# Asfaloth_L2_AVI_ver0_0.net
KiCad netlist of a schematic drawn in Altium Designer
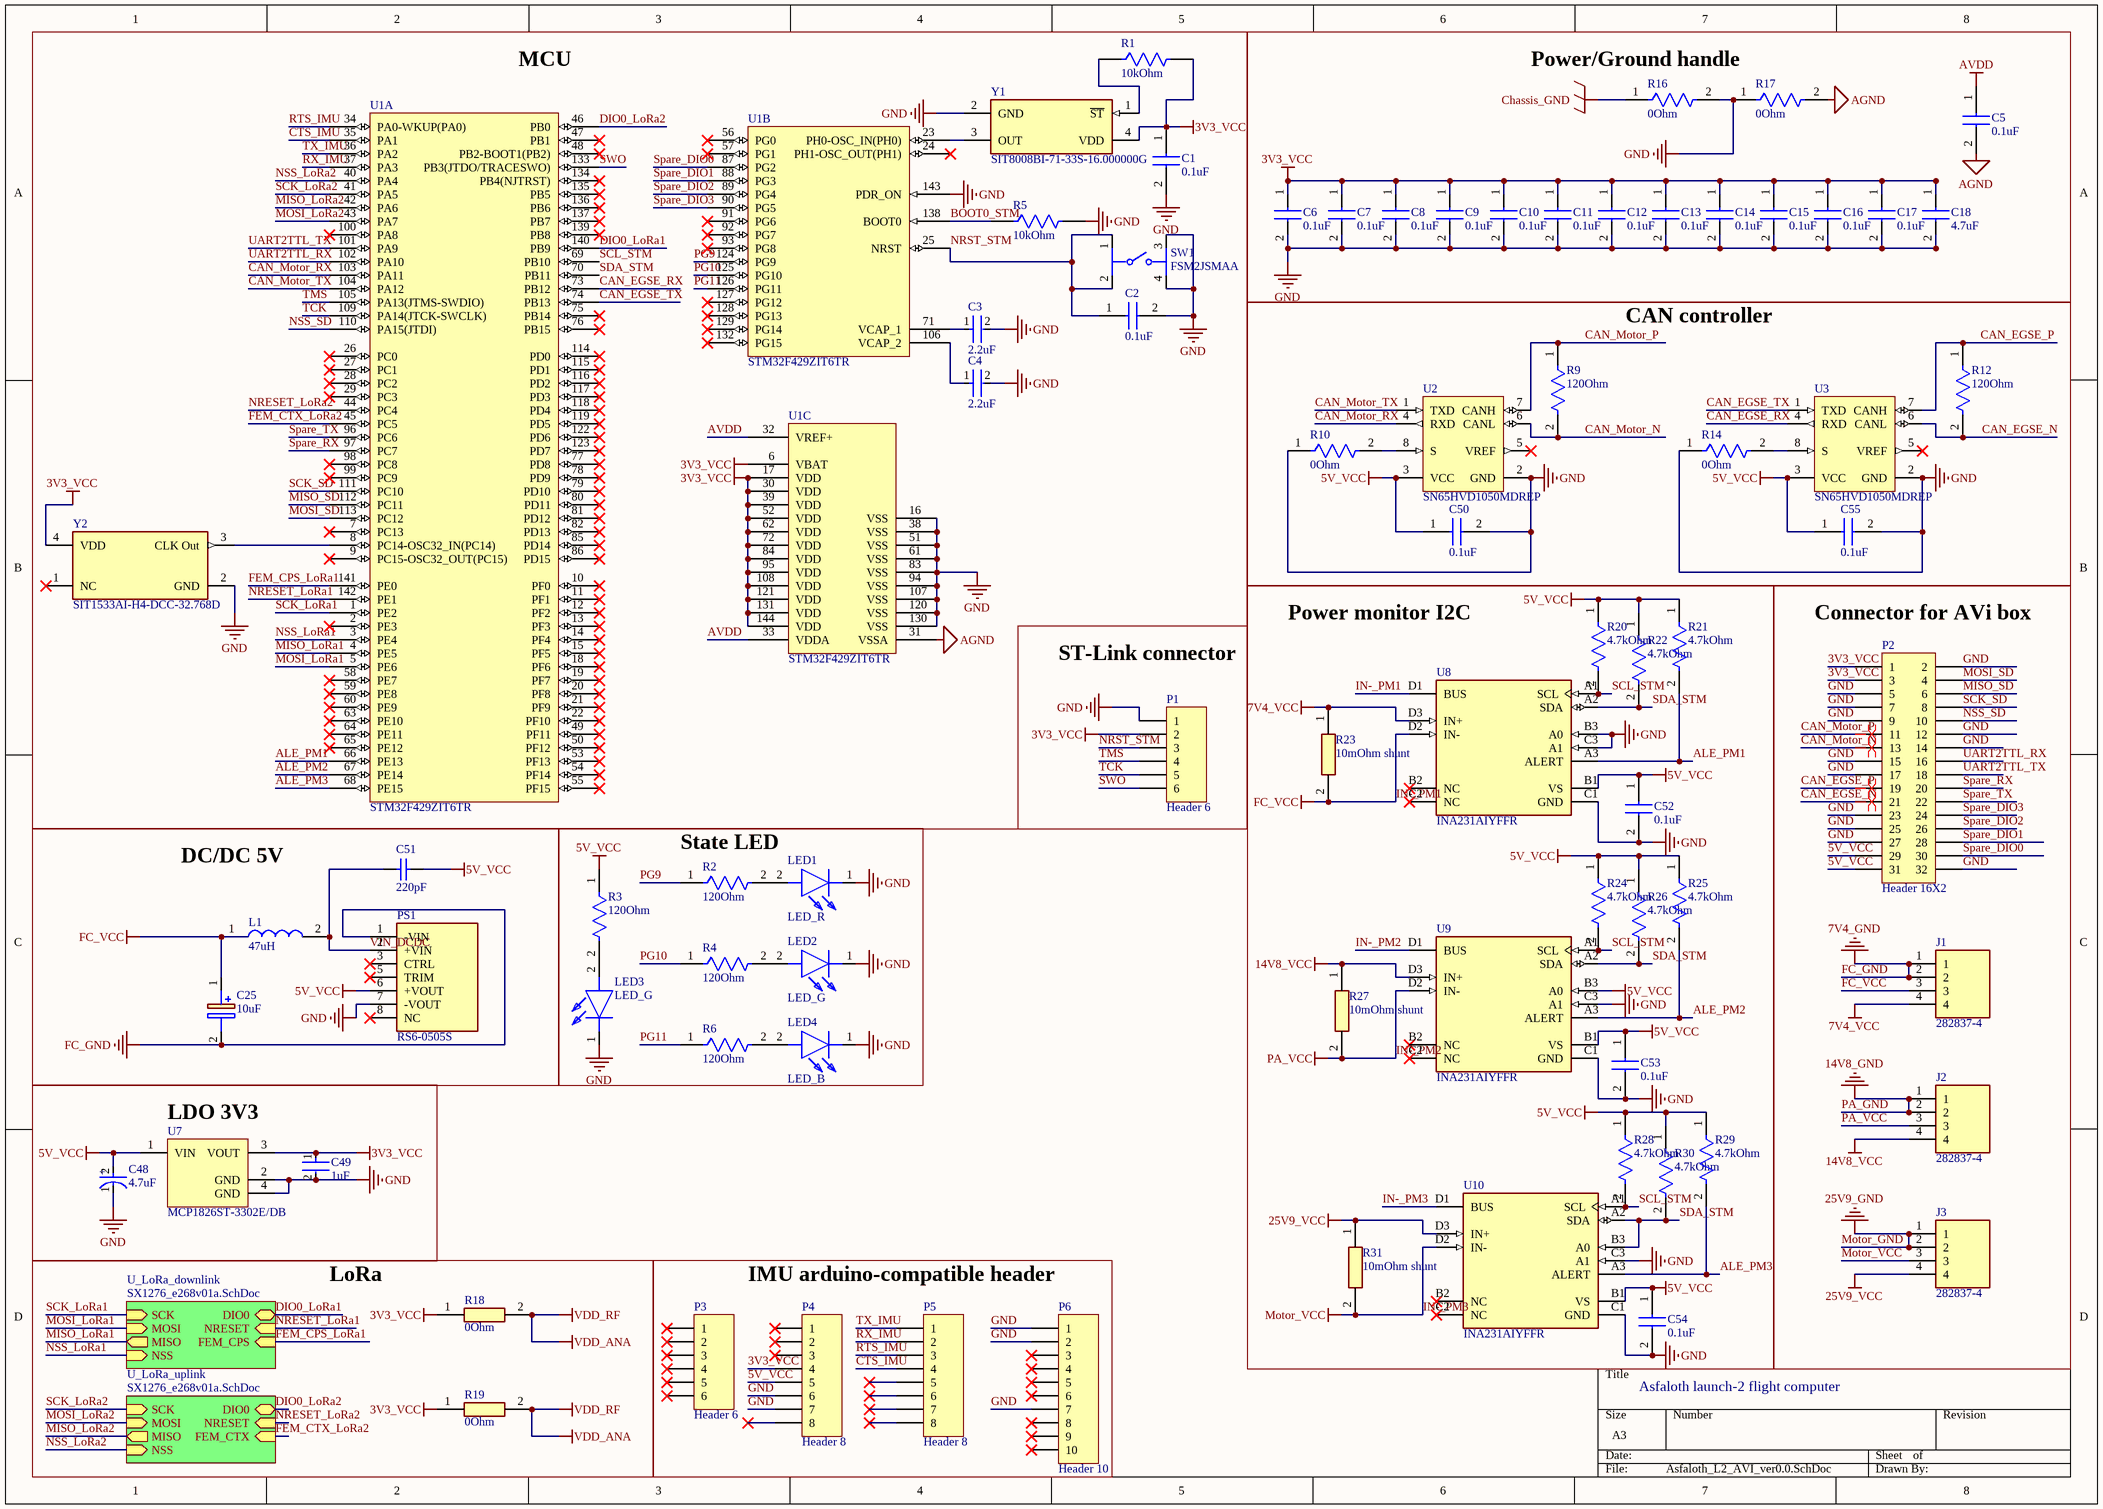
[diagram p0: Asfaloth_L2_AVI_ver0.0.SchDoc]

(export (version "E")
  (design (tool "Eeschema 10.0.6"))
  (components
    (comp (ref "C1")
      (value "0.1uF")
      (footprint "SamacSys:CAPC1608X87N")
      (description "Capacitor")
      (fields
        (field (name "MANUFACTURER_PART_NUMBER") "C0603C104J4RECAUTO")
        (field (name "MOUSER PART NUMBER") "80-C0603C104J4RECAUT")
      )
      (libsource (lib "*") (part "C0603C104J4RECAUTO"))
    )
    (comp (ref "C2")
      (value "0.1uF")
      (footprint "SamacSys:CAPC1608X87N")
      (description "Capacitor")
      (fields
        (field (name "MANUFACTURER_PART_NUMBER") "C0603C104J4RECAUTO")
        (field (name "MOUSER PART NUMBER") "80-C0603C104J4RECAUT")
      )
      (libsource (lib "*") (part "C0603C104J4RECAUTO"))
    )
    (comp (ref "C3")
      (value "2.2uF")
      (footprint "FP-GRT155-0_2-IPC_C")
      (description "Multi-Layer Ceramic Capacitor 2.2uF 10V X6S ±10% 0402 Paper T/R")
      (fields (field (name "TOLERANCE") "10%"))
      (libsource (lib "Altium Content Vault") (part "02cd4be3c70576c341d710602a673aa"))
    )
    (comp (ref "C4")
      (value "2.2uF")
      (footprint "FP-GRT155-0_2-IPC_C")
      (description "Multi-Layer Ceramic Capacitor 2.2uF 10V X6S ±10% 0402 Paper T/R")
      (fields (field (name "TOLERANCE") "10%"))
      (libsource (lib "Altium Content Vault") (part "02cd4be3c70576c341d710602a673aa"))
    )
    (comp (ref "C5")
      (value "0.1uF")
      (footprint "SamacSys:CAPC1608X87N")
      (description "Capacitor")
      (fields
        (field (name "MANUFACTURER_PART_NUMBER") "C0603C104J4RECAUTO")
        (field (name "MOUSER PART NUMBER") "80-C0603C104J4RECAUT")
      )
      (libsource (lib "*") (part "C0603C104J4RECAUTO"))
    )
    (comp (ref "C6")
      (value "0.1uF")
      (footprint "SamacSys:CAPC1608X87N")
      (description "Capacitor")
      (fields
        (field (name "MANUFACTURER_PART_NUMBER") "C0603C104J4RECAUTO")
        (field (name "MOUSER PART NUMBER") "80-C0603C104J4RECAUT")
      )
      (libsource (lib "*") (part "C0603C104J4RECAUTO"))
    )
    (comp (ref "C7")
      (value "0.1uF")
      (footprint "SamacSys:CAPC1608X87N")
      (description "Capacitor")
      (fields
        (field (name "MANUFACTURER_PART_NUMBER") "C0603C104J4RECAUTO")
        (field (name "MOUSER PART NUMBER") "80-C0603C104J4RECAUT")
      )
      (libsource (lib "*") (part "C0603C104J4RECAUTO"))
    )
    (comp (ref "C8")
      (value "0.1uF")
      (footprint "SamacSys:CAPC1608X87N")
      (description "Capacitor")
      (fields
        (field (name "MANUFACTURER_PART_NUMBER") "C0603C104J4RECAUTO")
        (field (name "MOUSER PART NUMBER") "80-C0603C104J4RECAUT")
      )
      (libsource (lib "*") (part "C0603C104J4RECAUTO"))
    )
    (comp (ref "C9")
      (value "0.1uF")
      (footprint "SamacSys:CAPC1608X87N")
      (description "Capacitor")
      (fields
        (field (name "MANUFACTURER_PART_NUMBER") "C0603C104J4RECAUTO")
        (field (name "MOUSER PART NUMBER") "80-C0603C104J4RECAUT")
      )
      (libsource (lib "*") (part "C0603C104J4RECAUTO"))
    )
    (comp (ref "C10")
      (value "0.1uF")
      (footprint "SamacSys:CAPC1608X87N")
      (description "Capacitor")
      (fields
        (field (name "MANUFACTURER_PART_NUMBER") "C0603C104J4RECAUTO")
        (field (name "MOUSER PART NUMBER") "80-C0603C104J4RECAUT")
      )
      (libsource (lib "*") (part "C0603C104J4RECAUTO"))
    )
    (comp (ref "C11")
      (value "0.1uF")
      (footprint "SamacSys:CAPC1608X87N")
      (description "Capacitor")
      (fields
        (field (name "MANUFACTURER_PART_NUMBER") "C0603C104J4RECAUTO")
        (field (name "MOUSER PART NUMBER") "80-C0603C104J4RECAUT")
      )
      (libsource (lib "*") (part "C0603C104J4RECAUTO"))
    )
    (comp (ref "C12")
      (value "0.1uF")
      (footprint "SamacSys:CAPC1608X87N")
      (description "Capacitor")
      (fields
        (field (name "MANUFACTURER_PART_NUMBER") "C0603C104J4RECAUTO")
        (field (name "MOUSER PART NUMBER") "80-C0603C104J4RECAUT")
      )
      (libsource (lib "*") (part "C0603C104J4RECAUTO"))
    )
    (comp (ref "C13")
      (value "0.1uF")
      (footprint "SamacSys:CAPC1608X87N")
      (description "Capacitor")
      (fields
        (field (name "MANUFACTURER_PART_NUMBER") "C0603C104J4RECAUTO")
        (field (name "MOUSER PART NUMBER") "80-C0603C104J4RECAUT")
      )
      (libsource (lib "*") (part "C0603C104J4RECAUTO"))
    )
    (comp (ref "C14")
      (value "0.1uF")
      (footprint "SamacSys:CAPC1608X87N")
      (description "Capacitor")
      (fields
        (field (name "MANUFACTURER_PART_NUMBER") "C0603C104J4RECAUTO")
        (field (name "MOUSER PART NUMBER") "80-C0603C104J4RECAUT")
      )
      (libsource (lib "*") (part "C0603C104J4RECAUTO"))
    )
    (comp (ref "C15")
      (value "0.1uF")
      (footprint "SamacSys:CAPC1608X87N")
      (description "Capacitor")
      (fields
        (field (name "MANUFACTURER_PART_NUMBER") "C0603C104J4RECAUTO")
        (field (name "MOUSER PART NUMBER") "80-C0603C104J4RECAUT")
      )
      (libsource (lib "*") (part "C0603C104J4RECAUTO"))
    )
    (comp (ref "C16")
      (value "0.1uF")
      (footprint "SamacSys:CAPC1608X87N")
      (description "Capacitor")
      (fields
        (field (name "MANUFACTURER_PART_NUMBER") "C0603C104J4RECAUTO")
        (field (name "MOUSER PART NUMBER") "80-C0603C104J4RECAUT")
      )
      (libsource (lib "*") (part "C0603C104J4RECAUTO"))
    )
    (comp (ref "C17")
      (value "0.1uF")
      (footprint "SamacSys:CAPC1608X87N")
      (description "Capacitor")
      (fields
        (field (name "MANUFACTURER_PART_NUMBER") "C0603C104J4RECAUTO")
        (field (name "MOUSER PART NUMBER") "80-C0603C104J4RECAUT")
      )
      (libsource (lib "*") (part "C0603C104J4RECAUTO"))
    )
    (comp (ref "C18")
      (value "4.7uF")
      (footprint "SamacSys:GRT188")
      (description "Capacitor")
      (fields
        (field (name "MANUFACTURER_PART_NUMBER") "GRT188C71C475KE13D")
        (field (name "MOUSER PART NUMBER") "81-GRT188C71C475KE13")
      )
      (libsource (lib "*") (part "GRT188C71C475KE13D"))
    )
    (comp (ref "C25")
      (value "10uF")
      (footprint "SamacSys:CAPAE830X650N")
      (description "Capacitor Polarised")
      (fields
        (field (name "MANUFACTURER_PART_NUMBER") "EEE-TG1J100P")
        (field (name "MOUSER PART NUMBER") "667-EEE-TG1J100P")
      )
      (libsource (lib "*") (part "EEE-TG1J100P"))
    )
    (comp (ref "C48")
      (value "4.7uF")
      (footprint "FP-TAJA-MFG")
      (description "4.7uF 16V  ±10% 4Ω 1206  SMD Tantalum Capacitor")
      (fields (field (name "TOLERANCE") "10%") (field (name "VOLTAGE") "16V"))
      (libsource (lib "Altium Content Vault") (part "203bc49f2ac43e59fd269a8c329ed05"))
    )
    (comp (ref "C49")
      (value "1uF")
      (footprint "FP-GCM21B-0_15-MFG")
      (description "Ceramic Capacitor for Automotive 1uF ±10% 16VDC X7R 0805 Embossed T/R")
      (fields (field (name "TOLERANCE") "10%"))
      (libsource (lib "Altium Content Vault") (part "02cd4be3c70576c341d710602a673aa"))
    )
    (comp (ref "C50")
      (value "0.1uF")
      (footprint "SamacSys:CAPC1608X87N")
      (description "Capacitor")
      (fields
        (field (name "MANUFACTURER_PART_NUMBER") "C0603C104J4RECAUTO")
        (field (name "MOUSER PART NUMBER") "80-C0603C104J4RECAUT")
      )
      (libsource (lib "*") (part "C0603C104J4RECAUTO"))
    )
    (comp (ref "C51")
      (value "220pF")
      (footprint "CAPC1608X87X35LL15T15")
      (fields (field (name "PART NUMBER") "C0603C221J5GACAUTO") (field (name "MANUFACTURER") "Kemet"))
      (libsource (lib "Altium Content Vault") (part "CAP"))
    )
    (comp (ref "C52")
      (value "0.1uF")
      (footprint "SamacSys:CAPC1608X87N")
      (description "Capacitor")
      (fields
        (field (name "MANUFACTURER_PART_NUMBER") "C0603C104J4RECAUTO")
        (field (name "MOUSER PART NUMBER") "80-C0603C104J4RECAUT")
      )
      (libsource (lib "*") (part "C0603C104J4RECAUTO"))
    )
    (comp (ref "C53")
      (value "0.1uF")
      (footprint "SamacSys:CAPC1608X87N")
      (description "Capacitor")
      (fields
        (field (name "MANUFACTURER_PART_NUMBER") "C0603C104J4RECAUTO")
        (field (name "MOUSER PART NUMBER") "80-C0603C104J4RECAUT")
      )
      (libsource (lib "*") (part "C0603C104J4RECAUTO"))
    )
    (comp (ref "C54")
      (value "0.1uF")
      (footprint "SamacSys:CAPC1608X87N")
      (description "Capacitor")
      (fields
        (field (name "MANUFACTURER_PART_NUMBER") "C0603C104J4RECAUTO")
        (field (name "MOUSER PART NUMBER") "80-C0603C104J4RECAUT")
      )
      (libsource (lib "*") (part "C0603C104J4RECAUTO"))
    )
    (comp (ref "C55")
      (value "0.1uF")
      (footprint "SamacSys:CAPC1608X87N")
      (description "Capacitor")
      (fields
        (field (name "MANUFACTURER_PART_NUMBER") "C0603C104J4RECAUTO")
        (field (name "MOUSER PART NUMBER") "80-C0603C104J4RECAUT")
      )
      (libsource (lib "*") (part "C0603C104J4RECAUTO"))
    )
    (comp (ref "J1")
      (value "282837-4")
      (footprint "SamacSys:2828374")
      (description "Connector")
      (fields (field (name "MOUSER PART NUMBER") "571-2828374"))
      (libsource (lib "SamacSys") (part "282837-4"))
    )
    (comp (ref "J2")
      (value "282837-4")
      (footprint "SamacSys:2828374")
      (description "Connector")
      (fields (field (name "MOUSER PART NUMBER") "571-2828374"))
      (libsource (lib "SamacSys") (part "282837-4"))
    )
    (comp (ref "J3")
      (value "282837-4")
      (footprint "SamacSys:2828374")
      (description "Connector")
      (fields (field (name "MOUSER PART NUMBER") "571-2828374"))
      (libsource (lib "SamacSys") (part "282837-4"))
    )
    (comp (ref "L1")
      (value "47uH")
      (footprint "SamacSys:SRR5228A")
      (description "Inductor")
      (fields
        (field (name "MANUFACTURER_PART_NUMBER") "SRR5228A-470M")
        (field (name "MOUSER PART NUMBER") "6521-SRR5228A-470M")
      )
      (libsource (lib "*") (part "SRR5228A-470M"))
    )
    (comp (ref "LED1")
      (value "LED_R")
      (footprint "SamacSys:LEDC2012X80N")
      (description "LED")
      (fields
        (field (name "MANUFACTURER_PART_NUMBER") "SML-H12V8TT86C")
        (field (name "MOUSER PART NUMBER") "755-SML-H12V8TT86C")
      )
      (libsource (lib "*") (part "SML-H12V8TT86C"))
    )
    (comp (ref "LED2")
      (value "LED_G")
      (footprint "SamacSys:LEDC2012X90N")
      (description "LED")
      (fields
        (field (name "MANUFACTURER_PART_NUMBER") "SML-H12P8TT86C")
        (field (name "MOUSER PART NUMBER") "755-SML-H12P8TT86C")
      )
      (libsource (lib "*") (part "SML-H12P8TT86C"))
    )
    (comp (ref "LED3")
      (value "LED_G")
      (footprint "SamacSys:LEDC2012X90N")
      (description "LED")
      (fields
        (field (name "MANUFACTURER_PART_NUMBER") "SML-H12P8TT86C")
        (field (name "MOUSER PART NUMBER") "755-SML-H12P8TT86C")
      )
      (libsource (lib "*") (part "SML-H12P8TT86C"))
    )
    (comp (ref "LED4")
      (value "LED_B")
      (footprint "SamacSys:LEDM2012X100N")
      (description "LED")
      (fields
        (field (name "MANUFACTURER_PART_NUMBER") "SMLMN2BCTT86C")
        (field (name "MOUSER PART NUMBER") "755-SMLMN2BCTT86C")
      )
      (libsource (lib "*") (part "SMLMN2BCTT86C"))
    )
    (comp (ref "P1")
      (value "Header 6")
      (footprint "HDR1X6")
      (description "Header, 6-Pin")
      (fields (field (name "PUBLISHER") "Altium Limited"))
      (libsource (lib "Miscellaneous Connectors") (part "Header 6"))
    )
    (comp (ref "P2")
      (value "Header 16X2")
      (footprint "HDR2X16")
      (description "Header, 16-Pin, Dual row")
      (fields (field (name "PUBLISHER") "Altium Limited"))
      (libsource (lib "Miscellaneous Connectors") (part "Header 16X2"))
    )
    (comp (ref "P3")
      (value "Header 6")
      (footprint "HDR1X6")
      (description "Header, 6-Pin")
      (fields (field (name "PUBLISHER") "Altium Limited"))
      (libsource (lib "Miscellaneous Connectors") (part "Header 6"))
    )
    (comp (ref "P4")
      (value "Header 8")
      (footprint "HDR1X8")
      (description "Header, 8-Pin")
      (fields (field (name "PUBLISHER") "Altium Limited"))
      (libsource (lib "Miscellaneous Connectors") (part "Header 8"))
    )
    (comp (ref "P5")
      (value "Header 8")
      (footprint "HDR1X8")
      (description "Header, 8-Pin")
      (fields (field (name "PUBLISHER") "Altium Limited"))
      (libsource (lib "Miscellaneous Connectors") (part "Header 8"))
    )
    (comp (ref "P6")
      (value "Header 10")
      (footprint "HDR1X10")
      (description "Header, 10-Pin")
      (fields (field (name "PUBLISHER") "Altium Limited"))
      (libsource (lib "Miscellaneous Connectors") (part "Header 10"))
    )
    (comp (ref "PS1")
      (value "RS6-0505S")
      (footprint "SamacSys:RS60505S")
      (description "Power Supply")
      (fields (field (name "MOUSER PART NUMBER") "919-RS6-0505S"))
      (libsource (lib "*") (part "RS6-0505S"))
    )
    (comp (ref "R1")
      (value "10kOhm")
      (footprint "FP-CRCW0805-e3-IPC_A")
      (description "RES Thick Film, 10kΩ, 1%, 0.125W, 100ppm/°C, 0805")
      (fields (field (name "TOLERANCE") "1%"))
      (libsource (lib "") (part "1029c3af85768c4190bb7ad29bc67b5_1"))
    )
    (comp (ref "R2")
      (value "120Ohm")
      (footprint "FP-ERJ2RK-MFG")
      (description "RES SMD 120 OHM 1% 1/10W 0402")
      (fields (field (name "TOLERANCE") "1%"))
      (libsource (lib "Altium Content Vault") (part "1029c3af85768c4190bb7ad29bc67b5"))
    )
    (comp (ref "R3")
      (value "120Ohm")
      (footprint "FP-ERJ2RK-MFG")
      (description "RES SMD 120 OHM 1% 1/10W 0402")
      (fields (field (name "TOLERANCE") "1%"))
      (libsource (lib "Altium Content Vault") (part "1029c3af85768c4190bb7ad29bc67b5"))
    )
    (comp (ref "R4")
      (value "120Ohm")
      (footprint "FP-ERJ2RK-MFG")
      (description "RES SMD 120 OHM 1% 1/10W 0402")
      (fields (field (name "TOLERANCE") "1%"))
      (libsource (lib "Altium Content Vault") (part "1029c3af85768c4190bb7ad29bc67b5"))
    )
    (comp (ref "R5")
      (value "10kOhm")
      (footprint "FP-CRCW0805-e3-IPC_A")
      (description "RES Thick Film, 10kΩ, 1%, 0.125W, 100ppm/°C, 0805")
      (fields (field (name "TOLERANCE") "1%"))
      (libsource (lib "") (part "1029c3af85768c4190bb7ad29bc67b5_1"))
    )
    (comp (ref "R6")
      (value "120Ohm")
      (footprint "FP-ERJ2RK-MFG")
      (description "RES SMD 120 OHM 1% 1/10W 0402")
      (fields (field (name "TOLERANCE") "1%"))
      (libsource (lib "Altium Content Vault") (part "1029c3af85768c4190bb7ad29bc67b5"))
    )
    (comp (ref "R9")
      (value "120Ohm")
      (footprint "FP-ERJ2RK-MFG")
      (description "RES SMD 120 OHM 1% 1/10W 0402")
      (fields (field (name "TOLERANCE") "1%"))
      (libsource (lib "Altium Content Vault") (part "1029c3af85768c4190bb7ad29bc67b5"))
    )
    (comp (ref "R10")
      (value "0Ohm")
      (footprint "FP-AC0603-0_55-IPC_A")
      (description "RES SMD 0 OHM JUMPER 1/10W 0603")
      (fields (field (name "TOLERANCE") "1%"))
      (libsource (lib "Altium Content Vault") (part "1029c3af85768c4190bb7ad29bc67b5"))
    )
    (comp (ref "R12")
      (value "120Ohm")
      (footprint "FP-ERJ2RK-MFG")
      (description "RES SMD 120 OHM 1% 1/10W 0402")
      (fields (field (name "TOLERANCE") "1%"))
      (libsource (lib "Altium Content Vault") (part "1029c3af85768c4190bb7ad29bc67b5"))
    )
    (comp (ref "R14")
      (value "0Ohm")
      (footprint "FP-AC0603-0_55-IPC_A")
      (description "RES SMD 0 OHM JUMPER 1/10W 0603")
      (fields (field (name "TOLERANCE") "1%"))
      (libsource (lib "Altium Content Vault") (part "1029c3af85768c4190bb7ad29bc67b5"))
    )
    (comp (ref "R16")
      (value "0Ohm")
      (footprint "FP-AC0603-0_55-IPC_A")
      (description "RES SMD 0 OHM JUMPER 1/10W 0603")
      (fields (field (name "TOLERANCE") "1%"))
      (libsource (lib "Altium Content Vault") (part "1029c3af85768c4190bb7ad29bc67b5"))
    )
    (comp (ref "R17")
      (value "0Ohm")
      (footprint "FP-AC0603-0_55-IPC_A")
      (description "RES SMD 0 OHM JUMPER 1/10W 0603")
      (fields (field (name "TOLERANCE") "1%"))
      (libsource (lib "Altium Content Vault") (part "1029c3af85768c4190bb7ad29bc67b5"))
    )
    (comp (ref "R18")
      (value "0Ohm")
      (footprint "SamacSys:RESC3216X60N")
      (description "Resistor")
      (fields
        (field (name "MANUFACTURER_PART_NUMBER") "RCA12060000ZSEA")
        (field (name "MOUSER PART NUMBER") "71-RCA12060000ZSEA")
      )
      (libsource (lib "*") (part "RCA12060000ZSEA"))
    )
    (comp (ref "R19")
      (value "0Ohm")
      (footprint "SamacSys:RESC3216X60N")
      (description "Resistor")
      (fields
        (field (name "MANUFACTURER_PART_NUMBER") "RCA12060000ZSEA")
        (field (name "MOUSER PART NUMBER") "71-RCA12060000ZSEA")
      )
      (libsource (lib "*") (part "RCA12060000ZSEA"))
    )
    (comp (ref "R20")
      (value "4.7kOhm")
      (footprint "FP-KTR03-IPC_C")
      (description "Res Thick Film 0603 4.7kΩ 5% 0.1W ±200ppm/°C Automotive Paper T/R")
      (fields (field (name "TOLERANCE") "5%"))
      (libsource (lib "Altium Content Vault") (part "1029c3af85768c4190bb7ad29bc67b5"))
    )
    (comp (ref "R21")
      (value "4.7kOhm")
      (footprint "FP-KTR03-IPC_C")
      (description "Res Thick Film 0603 4.7kΩ 5% 0.1W ±200ppm/°C Automotive Paper T/R")
      (fields (field (name "TOLERANCE") "5%"))
      (libsource (lib "Altium Content Vault") (part "1029c3af85768c4190bb7ad29bc67b5"))
    )
    (comp (ref "R22")
      (value "4.7kOhm")
      (footprint "FP-KTR03-IPC_C")
      (description "Res Thick Film 0603 4.7kΩ 5% 0.1W ±200ppm/°C Automotive Paper T/R")
      (fields (field (name "TOLERANCE") "5%"))
      (libsource (lib "Altium Content Vault") (part "1029c3af85768c4190bb7ad29bc67b5"))
    )
    (comp (ref "R23")
      (value "10mOhm shunt")
      (footprint "SamacSys:CSS0805FT10L0")
      (description "Resistor")
      (fields
        (field (name "MANUFACTURER_PART_NUMBER") "CSS0805FT10L0")
        (field (name "MOUSER PART NUMBER") "708-CSS0805FT10L0")
      )
      (libsource (lib "*") (part "CSS0805FT10L0"))
    )
    (comp (ref "R24")
      (value "4.7kOhm")
      (footprint "FP-KTR03-IPC_C")
      (description "Res Thick Film 0603 4.7kΩ 5% 0.1W ±200ppm/°C Automotive Paper T/R")
      (fields (field (name "TOLERANCE") "5%"))
      (libsource (lib "Altium Content Vault") (part "1029c3af85768c4190bb7ad29bc67b5"))
    )
    (comp (ref "R25")
      (value "4.7kOhm")
      (footprint "FP-KTR03-IPC_C")
      (description "Res Thick Film 0603 4.7kΩ 5% 0.1W ±200ppm/°C Automotive Paper T/R")
      (fields (field (name "TOLERANCE") "5%"))
      (libsource (lib "Altium Content Vault") (part "1029c3af85768c4190bb7ad29bc67b5"))
    )
    (comp (ref "R26")
      (value "4.7kOhm")
      (footprint "FP-KTR03-IPC_C")
      (description "Res Thick Film 0603 4.7kΩ 5% 0.1W ±200ppm/°C Automotive Paper T/R")
      (fields (field (name "TOLERANCE") "5%"))
      (libsource (lib "Altium Content Vault") (part "1029c3af85768c4190bb7ad29bc67b5"))
    )
    (comp (ref "R27")
      (value "10mOhm shunt")
      (footprint "SamacSys:CSS0805FT10L0")
      (description "Resistor")
      (fields
        (field (name "MANUFACTURER_PART_NUMBER") "CSS0805FT10L0")
        (field (name "MOUSER PART NUMBER") "708-CSS0805FT10L0")
      )
      (libsource (lib "*") (part "CSS0805FT10L0"))
    )
    (comp (ref "R28")
      (value "4.7kOhm")
      (footprint "FP-KTR03-IPC_C")
      (description "Res Thick Film 0603 4.7kΩ 5% 0.1W ±200ppm/°C Automotive Paper T/R")
      (fields (field (name "TOLERANCE") "5%"))
      (libsource (lib "Altium Content Vault") (part "1029c3af85768c4190bb7ad29bc67b5"))
    )
    (comp (ref "R29")
      (value "4.7kOhm")
      (footprint "FP-KTR03-IPC_C")
      (description "Res Thick Film 0603 4.7kΩ 5% 0.1W ±200ppm/°C Automotive Paper T/R")
      (fields (field (name "TOLERANCE") "5%"))
      (libsource (lib "Altium Content Vault") (part "1029c3af85768c4190bb7ad29bc67b5"))
    )
    (comp (ref "R30")
      (value "4.7kOhm")
      (footprint "FP-KTR03-IPC_C")
      (description "Res Thick Film 0603 4.7kΩ 5% 0.1W ±200ppm/°C Automotive Paper T/R")
      (fields (field (name "TOLERANCE") "5%"))
      (libsource (lib "Altium Content Vault") (part "1029c3af85768c4190bb7ad29bc67b5"))
    )
    (comp (ref "R31")
      (value "10mOhm shunt")
      (footprint "SamacSys:CSS0805FT10L0")
      (description "Resistor")
      (fields
        (field (name "MANUFACTURER_PART_NUMBER") "CSS0805FT10L0")
        (field (name "MOUSER PART NUMBER") "708-CSS0805FT10L0")
      )
      (libsource (lib "*") (part "CSS0805FT10L0"))
    )
    (comp (ref "SW1")
      (value "FSM2JSMAA")
      (footprint "FP-FSM2JSMAA-MFG")
      (description "SWITCH TACTILE SPST-NO 0.05A 24V")
      (fields
        (field (name "MANUFACTURER") "TE Connectivity")
        (field (name "OCTOPART") "https://octopart.com/fsm2jsmaa-te+connectivity-41720620")
      )
      (libsource (lib "Altium Content Vault") (part "b8895f3f4cefb76e1819d2863dba89b"))
    )
    (comp (ref "U1")
      (value "STM32F429ZIT6TR")
      (footprint "STM-LQFP144_M")
      (libsource (lib "Altium Content Vault") (part "MC-ARM-STM32F4X7_9-LQFP144"))
    )
    (comp (ref "U2")
      (value "SN65HVD1050MDREP")
      (footprint "D0008A_M")
      (fields (field (name "MANUFACTURER") "Texas Instruments"))
      (libsource (lib "Altium Content Vault") (part "TI-SN65HVD1050-EP-SOIC_D-8"))
    )
    (comp (ref "U3")
      (value "SN65HVD1050MDREP")
      (footprint "D0008A_M")
      (fields (field (name "MANUFACTURER") "Texas Instruments"))
      (libsource (lib "Altium Content Vault") (part "TI-SN65HVD1050-EP-SOIC_D-8"))
    )
    (comp (ref "U7")
      (value "MCP1826ST-3302E/DB")
      (footprint "SOT-223-DB3_L")
      (libsource (lib "Altium Content Vault") (part "PM-LINEREG-MCP1826-IL4"))
    )
    (comp (ref "U8")
      (value "INA231AIYFFR")
      (footprint "FP-YFF0012-IPC_C")
      (description "IC CURRENT MONITOR 100DB 12DSBGA")
      (libsource (lib "Altium Content Vault") (part "45ec0a68ca5e232ea1aa11670bcc384"))
    )
    (comp (ref "U9")
      (value "INA231AIYFFR")
      (footprint "FP-YFF0012-IPC_C")
      (description "IC CURRENT MONITOR 100DB 12DSBGA")
      (libsource (lib "Altium Content Vault") (part "45ec0a68ca5e232ea1aa11670bcc384"))
    )
    (comp (ref "U10")
      (value "INA231AIYFFR")
      (footprint "FP-YFF0012-IPC_C")
      (description "IC CURRENT MONITOR 100DB 12DSBGA")
      (libsource (lib "Altium Content Vault") (part "45ec0a68ca5e232ea1aa11670bcc384"))
    )
    (comp (ref "Y1")
      (value "SIT8008BI-71-33S-16.000000G")
      (footprint "FP-SiT8008-7-MFG")
      (description "MEMS OSC XO 16.0000MHZ H/LV-CMOS")
      (libsource (lib "Altium Content Vault") (part "0b6e30c8c84b5cf713c4e00c700effb"))
    )
    (comp (ref "Y2")
      (value "SIT1533AI-H4-DCC-32.768D")
      (footprint "FP-SiT1533-H-MFG")
      (description "MEMS OSC XO 32.7680KHZ LVCMOS")
      (libsource (lib "Altium Content Vault") (part "d6da4f2ecb1e1a500d17fb349569450"))
    )
  )
  (nets
    (net (code "1") (name "/ALE_PM1") (class "Default")
      (node (ref "R21") (pin "2") (pinfunction "2_2") (pintype "passive"))
      (node (ref "U1") (pin "66") (pinfunction "PE13_66") (pintype "bidirectional"))
      (node (ref "U8") (pin "A3") (pinfunction "ALERT_A3") (pintype "open_collector"))
    )
    (net (code "2") (name "/ALE_PM2") (class "Default")
      (node (ref "R25") (pin "2") (pinfunction "2_2") (pintype "passive"))
      (node (ref "U1") (pin "67") (pinfunction "PE14_67") (pintype "bidirectional"))
      (node (ref "U9") (pin "A3") (pinfunction "ALERT_A3") (pintype "open_collector"))
    )
    (net (code "3") (name "/ALE_PM3") (class "Default")
      (node (ref "R29") (pin "2") (pinfunction "2_2") (pintype "passive"))
      (node (ref "U1") (pin "68") (pinfunction "PE15_68") (pintype "bidirectional"))
      (node (ref "U10") (pin "A3") (pinfunction "ALERT_A3") (pintype "open_collector"))
    )
    (net (code "4") (name "/BOOT0_STM") (class "Default")
      (node (ref "R5") (pin "1") (pinfunction "1_1") (pintype "passive"))
      (node (ref "U1") (pin "138") (pinfunction "BOOT0_138") (pintype "input"))
    )
    (net (code "5") (name "/CAN_EGSE_N") (class "Default")
      (node (ref "P2") (pin "21") (pinfunction "21_21") (pintype "passive"))
      (node (ref "R12") (pin "2") (pinfunction "2_2") (pintype "passive"))
      (node (ref "U3") (pin "6") (pinfunction "CANL_6") (pintype "bidirectional"))
    )
    (net (code "6") (name "/CAN_EGSE_P") (class "Default")
      (node (ref "P2") (pin "19") (pinfunction "19_19") (pintype "passive"))
      (node (ref "R12") (pin "1") (pinfunction "1_1") (pintype "passive"))
      (node (ref "U3") (pin "7") (pinfunction "CANH_7") (pintype "bidirectional"))
    )
    (net (code "7") (name "/CAN_EGSE_RX") (class "Default")
      (node (ref "U1") (pin "73") (pinfunction "PB12_73") (pintype "bidirectional"))
      (node (ref "U3") (pin "4") (pinfunction "RXD_4") (pintype "output"))
    )
    (net (code "8") (name "/CAN_EGSE_TX") (class "Default")
      (node (ref "U1") (pin "74") (pinfunction "PB13_74") (pintype "bidirectional"))
      (node (ref "U3") (pin "1") (pinfunction "TXD_1") (pintype "input"))
    )
    (net (code "9") (name "/CAN_Motor_N") (class "Default")
      (node (ref "P2") (pin "13") (pinfunction "13_13") (pintype "passive"))
      (node (ref "R9") (pin "2") (pinfunction "2_2") (pintype "passive"))
      (node (ref "U2") (pin "6") (pinfunction "CANL_6") (pintype "bidirectional"))
    )
    (net (code "10") (name "/CAN_Motor_P") (class "Default")
      (node (ref "P2") (pin "11") (pinfunction "11_11") (pintype "passive"))
      (node (ref "R9") (pin "1") (pinfunction "1_1") (pintype "passive"))
      (node (ref "U2") (pin "7") (pinfunction "CANH_7") (pintype "bidirectional"))
    )
    (net (code "11") (name "/CAN_Motor_RX") (class "Default")
      (node (ref "U1") (pin "103") (pinfunction "PA11_103") (pintype "bidirectional"))
      (node (ref "U2") (pin "4") (pinfunction "RXD_4") (pintype "output"))
    )
    (net (code "12") (name "/CAN_Motor_TX") (class "Default")
      (node (ref "U1") (pin "104") (pinfunction "PA12_104") (pintype "bidirectional"))
      (node (ref "U2") (pin "1") (pinfunction "TXD_1") (pintype "input"))
    )
    (net (code "13") (name "/CTS_IMU") (class "Default")
      (node (ref "P5") (pin "4") (pinfunction "4_4") (pintype "passive"))
      (node (ref "U1") (pin "35") (pinfunction "PA1_35") (pintype "bidirectional"))
    )
    (net (code "14") (name "/DIO0_LoRa1") (class "Default")
      (node (ref "U1") (pin "140") (pinfunction "PB9_140") (pintype "bidirectional"))
    )
    (net (code "15") (name "/DIO0_LoRa2") (class "Default")
      (node (ref "U1") (pin "46") (pinfunction "PB0_46") (pintype "bidirectional"))
    )
    (net (code "16") (name "/FEM_CPS_LoRa1") (class "Default")
      (node (ref "U1") (pin "141") (pinfunction "PE0_141") (pintype "bidirectional"))
    )
    (net (code "17") (name "/FEM_CTX_LoRa2") (class "Default")
      (node (ref "U1") (pin "45") (pinfunction "PC5_45") (pintype "bidirectional"))
    )
    (net (code "18") (name "/MISO_LoRa1") (class "Default")
      (node (ref "U1") (pin "4") (pinfunction "PE5_4") (pintype "bidirectional"))
    )
    (net (code "19") (name "/MISO_LoRa2") (class "Default")
      (node (ref "U1") (pin "42") (pinfunction "PA6_42") (pintype "bidirectional"))
    )
    (net (code "20") (name "/MISO_SD") (class "Default")
      (node (ref "P2") (pin "6") (pinfunction "6_6") (pintype "passive"))
      (node (ref "U1") (pin "112") (pinfunction "PC11_112") (pintype "bidirectional"))
    )
    (net (code "21") (name "/MOSI_LoRa1") (class "Default")
      (node (ref "U1") (pin "5") (pinfunction "PE6_5") (pintype "bidirectional"))
    )
    (net (code "22") (name "/MOSI_LoRa2") (class "Default")
      (node (ref "U1") (pin "43") (pinfunction "PA7_43") (pintype "bidirectional"))
    )
    (net (code "23") (name "/MOSI_SD") (class "Default")
      (node (ref "P2") (pin "4") (pinfunction "4_4") (pintype "passive"))
      (node (ref "U1") (pin "113") (pinfunction "PC12_113") (pintype "bidirectional"))
    )
    (net (code "24") (name "/NRESET_LoRa1") (class "Default")
      (node (ref "U1") (pin "142") (pinfunction "PE1_142") (pintype "bidirectional"))
    )
    (net (code "25") (name "/NRESET_LoRa2") (class "Default")
      (node (ref "U1") (pin "44") (pinfunction "PC4_44") (pintype "bidirectional"))
    )
    (net (code "26") (name "/NRST_STM") (class "Default")
      (node (ref "C2") (pin "1") (pinfunction "1_1") (pintype "passive"))
      (node (ref "P1") (pin "3") (pinfunction "3_3") (pintype "passive"))
      (node (ref "SW1") (pin "1") (pinfunction "1_1") (pintype "passive"))
      (node (ref "SW1") (pin "2") (pinfunction "2_2") (pintype "passive"))
      (node (ref "U1") (pin "25") (pinfunction "NRST_25") (pintype "bidirectional"))
    )
    (net (code "27") (name "/NSS_LoRa1") (class "Default")
      (node (ref "U1") (pin "3") (pinfunction "PE4_3") (pintype "bidirectional"))
    )
    (net (code "28") (name "/NSS_LoRa2") (class "Default")
      (node (ref "U1") (pin "40") (pinfunction "PA4_40") (pintype "bidirectional"))
    )
    (net (code "29") (name "/NSS_SD") (class "Default")
      (node (ref "P2") (pin "10") (pinfunction "10_10") (pintype "passive"))
      (node (ref "U1") (pin "110") (pinfunction "PA15(JTDI)_110") (pintype "bidirectional"))
    )
    (net (code "30") (name "/PG9") (class "Default")
      (node (ref "R2") (pin "1") (pinfunction "1_1") (pintype "passive"))
      (node (ref "U1") (pin "124") (pinfunction "PG9_124") (pintype "bidirectional"))
    )
    (net (code "31") (name "/PG10") (class "Default")
      (node (ref "R4") (pin "1") (pinfunction "1_1") (pintype "passive"))
      (node (ref "U1") (pin "125") (pinfunction "PG10_125") (pintype "bidirectional"))
    )
    (net (code "32") (name "/PG11") (class "Default")
      (node (ref "R6") (pin "1") (pinfunction "1_1") (pintype "passive"))
      (node (ref "U1") (pin "126") (pinfunction "PG11_126") (pintype "bidirectional"))
    )
    (net (code "33") (name "/RTS_IMU") (class "Default")
      (node (ref "P5") (pin "3") (pinfunction "3_3") (pintype "passive"))
      (node (ref "U1") (pin "34") (pinfunction "PA0-WKUP(PA0)_34") (pintype "bidirectional"))
    )
    (net (code "34") (name "/RX_IMU") (class "Default")
      (node (ref "P5") (pin "2") (pinfunction "2_2") (pintype "passive"))
      (node (ref "U1") (pin "37") (pinfunction "PA3_37") (pintype "bidirectional"))
    )
    (net (code "35") (name "/SCK_LoRa1") (class "Default")
      (node (ref "U1") (pin "1") (pinfunction "PE2_1") (pintype "bidirectional"))
    )
    (net (code "36") (name "/SCK_LoRa2") (class "Default")
      (node (ref "U1") (pin "41") (pinfunction "PA5_41") (pintype "bidirectional"))
    )
    (net (code "37") (name "/SCK_SD") (class "Default")
      (node (ref "P2") (pin "8") (pinfunction "8_8") (pintype "passive"))
      (node (ref "U1") (pin "111") (pinfunction "PC10_111") (pintype "bidirectional"))
    )
    (net (code "38") (name "/SCL_STM") (class "Default")
      (node (ref "R20") (pin "2") (pinfunction "2_2") (pintype "passive"))
      (node (ref "R24") (pin "2") (pinfunction "2_2") (pintype "passive"))
      (node (ref "R28") (pin "2") (pinfunction "2_2") (pintype "passive"))
      (node (ref "U1") (pin "69") (pinfunction "PB10_69") (pintype "bidirectional"))
      (node (ref "U10") (pin "A1") (pinfunction "SCL_A1") (pintype "input"))
      (node (ref "U8") (pin "A1") (pinfunction "SCL_A1") (pintype "input"))
      (node (ref "U9") (pin "A1") (pinfunction "SCL_A1") (pintype "input"))
    )
    (net (code "39") (name "/SDA_STM") (class "Default")
      (node (ref "R22") (pin "2") (pinfunction "2_2") (pintype "passive"))
      (node (ref "R26") (pin "2") (pinfunction "2_2") (pintype "passive"))
      (node (ref "R30") (pin "2") (pinfunction "2_2") (pintype "passive"))
      (node (ref "U1") (pin "70") (pinfunction "PB11_70") (pintype "bidirectional"))
      (node (ref "U10") (pin "A2") (pinfunction "SDA_A2") (pintype "bidirectional"))
      (node (ref "U10") (pin "B3") (pinfunction "A0_B3") (pintype "input"))
      (node (ref "U8") (pin "A2") (pinfunction "SDA_A2") (pintype "bidirectional"))
      (node (ref "U9") (pin "A2") (pinfunction "SDA_A2") (pintype "bidirectional"))
    )
    (net (code "40") (name "/SWO") (class "Default")
      (node (ref "P1") (pin "6") (pinfunction "6_6") (pintype "passive"))
      (node (ref "U1") (pin "133") (pinfunction "PB3(JTDO/TRACESWO)_133") (pintype "bidirectional"))
    )
    (net (code "41") (name "/Spare_DIO0") (class "Default")
      (node (ref "P2") (pin "30") (pinfunction "30_30") (pintype "passive"))
      (node (ref "U1") (pin "87") (pinfunction "PG2_87") (pintype "bidirectional"))
    )
    (net (code "42") (name "/Spare_DIO1") (class "Default")
      (node (ref "P2") (pin "28") (pinfunction "28_28") (pintype "passive"))
      (node (ref "U1") (pin "88") (pinfunction "PG3_88") (pintype "bidirectional"))
    )
    (net (code "43") (name "/Spare_DIO2") (class "Default")
      (node (ref "P2") (pin "26") (pinfunction "26_26") (pintype "passive"))
      (node (ref "U1") (pin "89") (pinfunction "PG4_89") (pintype "bidirectional"))
    )
    (net (code "44") (name "/Spare_DIO3") (class "Default")
      (node (ref "P2") (pin "24") (pinfunction "24_24") (pintype "passive"))
      (node (ref "U1") (pin "90") (pinfunction "PG5_90") (pintype "bidirectional"))
    )
    (net (code "45") (name "/Spare_RX") (class "Default")
      (node (ref "P2") (pin "20") (pinfunction "20_20") (pintype "passive"))
      (node (ref "U1") (pin "97") (pinfunction "PC7_97") (pintype "bidirectional"))
    )
    (net (code "46") (name "/Spare_TX") (class "Default")
      (node (ref "P2") (pin "22") (pinfunction "22_22") (pintype "passive"))
      (node (ref "U1") (pin "96") (pinfunction "PC6_96") (pintype "bidirectional"))
    )
    (net (code "47") (name "/TCK") (class "Default")
      (node (ref "P1") (pin "5") (pinfunction "5_5") (pintype "passive"))
      (node (ref "U1") (pin "109") (pinfunction "PA14(JTCK-SWCLK)_109") (pintype "bidirectional"))
    )
    (net (code "48") (name "/TMS") (class "Default")
      (node (ref "P1") (pin "4") (pinfunction "4_4") (pintype "passive"))
      (node (ref "U1") (pin "105") (pinfunction "PA13(JTMS-SWDIO)_105") (pintype "bidirectional"))
    )
    (net (code "49") (name "/TX_IMU") (class "Default")
      (node (ref "P5") (pin "1") (pinfunction "1_1") (pintype "passive"))
      (node (ref "U1") (pin "36") (pinfunction "PA2_36") (pintype "bidirectional"))
    )
    (net (code "50") (name "/UART2TTL_RX") (class "Default")
      (node (ref "P2") (pin "16") (pinfunction "16_16") (pintype "passive"))
      (node (ref "U1") (pin "102") (pinfunction "PA10_102") (pintype "bidirectional"))
    )
    (net (code "51") (name "/UART2TTL_TX") (class "Default")
      (node (ref "P2") (pin "18") (pinfunction "18_18") (pintype "passive"))
      (node (ref "U1") (pin "101") (pinfunction "PA9_101") (pintype "bidirectional"))
    )
    (net (code "52") (name "/VIN_DCDC") (class "Default")
      (node (ref "C51") (pin "1") (pinfunction "1_1") (pintype "passive"))
      (node (ref "L1") (pin "2") (pinfunction "2_2") (pintype "passive"))
      (node (ref "PS1") (pin "2") (pinfunction "+VIN_2") (pintype "passive"))
    )
    (net (code "53") (name "3V3_VCC") (class "Default")
      (node (ref "C1") (pin "1") (pinfunction "1_1") (pintype "passive"))
      (node (ref "C10") (pin "1") (pinfunction "1_1") (pintype "passive"))
      (node (ref "C11") (pin "1") (pinfunction "1_1") (pintype "passive"))
      (node (ref "C12") (pin "1") (pinfunction "1_1") (pintype "passive"))
      (node (ref "C13") (pin "1") (pinfunction "1_1") (pintype "passive"))
      (node (ref "C14") (pin "1") (pinfunction "1_1") (pintype "passive"))
      (node (ref "C15") (pin "1") (pinfunction "1_1") (pintype "passive"))
      (node (ref "C16") (pin "1") (pinfunction "1_1") (pintype "passive"))
      (node (ref "C17") (pin "1") (pinfunction "1_1") (pintype "passive"))
      (node (ref "C18") (pin "1") (pinfunction "1_1") (pintype "passive"))
      (node (ref "C49") (pin "1") (pinfunction "1_1") (pintype "passive"))
      (node (ref "C6") (pin "1") (pinfunction "1_1") (pintype "passive"))
      (node (ref "C7") (pin "1") (pinfunction "1_1") (pintype "passive"))
      (node (ref "C8") (pin "1") (pinfunction "1_1") (pintype "passive"))
      (node (ref "C9") (pin "1") (pinfunction "1_1") (pintype "passive"))
      (node (ref "P1") (pin "2") (pinfunction "2_2") (pintype "passive"))
      (node (ref "P2") (pin "1") (pinfunction "1_1") (pintype "passive"))
      (node (ref "P2") (pin "3") (pinfunction "3_3") (pintype "passive"))
      (node (ref "P4") (pin "4") (pinfunction "4_4") (pintype "passive"))
      (node (ref "R1") (pin "2") (pinfunction "2_2") (pintype "passive"))
      (node (ref "R18") (pin "1") (pinfunction "1_1") (pintype "passive"))
      (node (ref "R19") (pin "1") (pinfunction "1_1") (pintype "passive"))
      (node (ref "U1") (pin "108") (pinfunction "VDD_108") (pintype "power_in"))
      (node (ref "U1") (pin "121") (pinfunction "VDD_121") (pintype "power_in"))
      (node (ref "U1") (pin "131") (pinfunction "VDD_131") (pintype "power_in"))
      (node (ref "U1") (pin "144") (pinfunction "VDD_144") (pintype "power_in"))
      (node (ref "U1") (pin "17") (pinfunction "VDD_17") (pintype "power_in"))
      (node (ref "U1") (pin "30") (pinfunction "VDD_30") (pintype "power_in"))
      (node (ref "U1") (pin "39") (pinfunction "VDD_39") (pintype "power_in"))
      (node (ref "U1") (pin "52") (pinfunction "VDD_52") (pintype "power_in"))
      (node (ref "U1") (pin "6") (pinfunction "VBAT_6") (pintype "power_in"))
      (node (ref "U1") (pin "62") (pinfunction "VDD_62") (pintype "power_in"))
      (node (ref "U1") (pin "72") (pinfunction "VDD_72") (pintype "power_in"))
      (node (ref "U1") (pin "84") (pinfunction "VDD_84") (pintype "power_in"))
      (node (ref "U1") (pin "95") (pinfunction "VDD_95") (pintype "power_in"))
      (node (ref "U7") (pin "3") (pinfunction "VOUT_3") (pintype "power_in"))
      (node (ref "Y1") (pin "4") (pinfunction "VDD_4") (pintype "power_in"))
      (node (ref "Y2") (pin "4") (pinfunction "VDD_4") (pintype "power_in"))
    )
    (net (code "54") (name "5V_VCC") (class "Default")
      (node (ref "C48") (pin "2") (pinfunction "A_2") (pintype "passive"))
      (node (ref "C50") (pin "1") (pinfunction "1_1") (pintype "passive"))
      (node (ref "C51") (pin "2") (pinfunction "2_2") (pintype "passive"))
      (node (ref "C52") (pin "1") (pinfunction "1_1") (pintype "passive"))
      (node (ref "C53") (pin "1") (pinfunction "1_1") (pintype "passive"))
      (node (ref "C54") (pin "1") (pinfunction "1_1") (pintype "passive"))
      (node (ref "C55") (pin "1") (pinfunction "1_1") (pintype "passive"))
      (node (ref "P2") (pin "29") (pinfunction "29_29") (pintype "passive"))
      (node (ref "P2") (pin "31") (pinfunction "31_31") (pintype "passive"))
      (node (ref "P4") (pin "5") (pinfunction "5_5") (pintype "passive"))
      (node (ref "PS1") (pin "6") (pinfunction "+VOUT_6") (pintype "passive"))
      (node (ref "R20") (pin "1") (pinfunction "1_1") (pintype "passive"))
      (node (ref "R21") (pin "1") (pinfunction "1_1") (pintype "passive"))
      (node (ref "R22") (pin "1") (pinfunction "1_1") (pintype "passive"))
      (node (ref "R24") (pin "1") (pinfunction "1_1") (pintype "passive"))
      (node (ref "R25") (pin "1") (pinfunction "1_1") (pintype "passive"))
      (node (ref "R26") (pin "1") (pinfunction "1_1") (pintype "passive"))
      (node (ref "R28") (pin "1") (pinfunction "1_1") (pintype "passive"))
      (node (ref "R29") (pin "1") (pinfunction "1_1") (pintype "passive"))
      (node (ref "R3") (pin "1") (pinfunction "1_1") (pintype "passive"))
      (node (ref "R30") (pin "1") (pinfunction "1_1") (pintype "passive"))
      (node (ref "U10") (pin "B1") (pinfunction "VS_B1") (pintype "power_in"))
      (node (ref "U2") (pin "3") (pinfunction "VCC_3") (pintype "power_in"))
      (node (ref "U3") (pin "3") (pinfunction "VCC_3") (pintype "power_in"))
      (node (ref "U7") (pin "1") (pinfunction "VIN_1") (pintype "power_in"))
      (node (ref "U8") (pin "B1") (pinfunction "VS_B1") (pintype "power_in"))
      (node (ref "U9") (pin "B1") (pinfunction "VS_B1") (pintype "power_in"))
      (node (ref "U9") (pin "B3") (pinfunction "A0_B3") (pintype "input"))
    )
    (net (code "55") (name "7V4_GND") (class "Default")
      (node (ref "C25") (pin "2") (pinfunction "-_2") (pintype "passive"))
      (node (ref "J1") (pin "1") (pinfunction "1_1") (pintype "passive"))
      (node (ref "J1") (pin "2") (pinfunction "2_2") (pintype "passive"))
      (node (ref "PS1") (pin "1") (pinfunction "-VIN_1") (pintype "passive"))
    )
    (net (code "56") (name "7V4_VCC") (class "Default")
      (node (ref "J1") (pin "4") (pinfunction "4_4") (pintype "passive"))
      (node (ref "R23") (pin "1") (pinfunction "1_1") (pintype "passive"))
      (node (ref "U8") (pin "D3") (pinfunction "IN+_D3") (pintype "input"))
    )
    (net (code "57") (name "14V8_GND") (class "Default")
      (node (ref "J2") (pin "1") (pinfunction "1_1") (pintype "passive"))
      (node (ref "J2") (pin "2") (pinfunction "2_2") (pintype "passive"))
    )
    (net (code "58") (name "14V8_VCC") (class "Default")
      (node (ref "J2") (pin "4") (pinfunction "4_4") (pintype "passive"))
      (node (ref "R27") (pin "1") (pinfunction "1_1") (pintype "passive"))
      (node (ref "U9") (pin "D3") (pinfunction "IN+_D3") (pintype "input"))
    )
    (net (code "59") (name "25V9_GND") (class "Default")
      (node (ref "J3") (pin "1") (pinfunction "1_1") (pintype "passive"))
      (node (ref "J3") (pin "2") (pinfunction "2_2") (pintype "passive"))
    )
    (net (code "60") (name "25V9_VCC") (class "Default")
      (node (ref "J3") (pin "4") (pinfunction "4_4") (pintype "passive"))
      (node (ref "R31") (pin "1") (pinfunction "1_1") (pintype "passive"))
      (node (ref "U10") (pin "D3") (pinfunction "IN+_D3") (pintype "input"))
    )
    (net (code "61") (name "AGND") (class "Default")
      (node (ref "C5") (pin "2") (pinfunction "2_2") (pintype "passive"))
      (node (ref "R17") (pin "2") (pinfunction "2_2") (pintype "passive"))
      (node (ref "U1") (pin "31") (pinfunction "VSSA_31") (pintype "power_in"))
    )
    (net (code "62") (name "AVDD") (class "Default")
      (node (ref "C5") (pin "1") (pinfunction "1_1") (pintype "passive"))
      (node (ref "U1") (pin "32") (pinfunction "VREF+_32") (pintype "power_in"))
      (node (ref "U1") (pin "33") (pinfunction "VDDA_33") (pintype "power_in"))
    )
    (net (code "63") (name "Chassis_GND") (class "Default")
      (node (ref "R16") (pin "1") (pinfunction "1_1") (pintype "passive"))
    )
    (net (code "64") (name "FC_VCC") (class "Default")
      (node (ref "C25") (pin "1") (pinfunction "+_1") (pintype "passive"))
      (node (ref "J1") (pin "3") (pinfunction "3_3") (pintype "passive"))
      (node (ref "L1") (pin "1") (pinfunction "1_1") (pintype "passive"))
      (node (ref "R23") (pin "2") (pinfunction "2_2") (pintype "passive"))
      (node (ref "U8") (pin "D1") (pinfunction "BUS_D1") (pintype "passive"))
      (node (ref "U8") (pin "D2") (pinfunction "IN-_D2") (pintype "input"))
    )
    (net (code "65") (name "GND") (class "Default")
      (node (ref "C1") (pin "2") (pinfunction "2_2") (pintype "passive"))
      (node (ref "C10") (pin "2") (pinfunction "2_2") (pintype "passive"))
      (node (ref "C11") (pin "2") (pinfunction "2_2") (pintype "passive"))
      (node (ref "C12") (pin "2") (pinfunction "2_2") (pintype "passive"))
      (node (ref "C13") (pin "2") (pinfunction "2_2") (pintype "passive"))
      (node (ref "C14") (pin "2") (pinfunction "2_2") (pintype "passive"))
      (node (ref "C15") (pin "2") (pinfunction "2_2") (pintype "passive"))
      (node (ref "C16") (pin "2") (pinfunction "2_2") (pintype "passive"))
      (node (ref "C17") (pin "2") (pinfunction "2_2") (pintype "passive"))
      (node (ref "C18") (pin "2") (pinfunction "2_2") (pintype "passive"))
      (node (ref "C2") (pin "2") (pinfunction "2_2") (pintype "passive"))
      (node (ref "C3") (pin "2") (pinfunction "2_2") (pintype "passive"))
      (node (ref "C4") (pin "2") (pinfunction "2_2") (pintype "passive"))
      (node (ref "C48") (pin "1") (pinfunction "C_1") (pintype "passive"))
      (node (ref "C49") (pin "2") (pinfunction "2_2") (pintype "passive"))
      (node (ref "C50") (pin "2") (pinfunction "2_2") (pintype "passive"))
      (node (ref "C52") (pin "2") (pinfunction "2_2") (pintype "passive"))
      (node (ref "C53") (pin "2") (pinfunction "2_2") (pintype "passive"))
      (node (ref "C54") (pin "2") (pinfunction "2_2") (pintype "passive"))
      (node (ref "C55") (pin "2") (pinfunction "2_2") (pintype "passive"))
      (node (ref "C6") (pin "2") (pinfunction "2_2") (pintype "passive"))
      (node (ref "C7") (pin "2") (pinfunction "2_2") (pintype "passive"))
      (node (ref "C8") (pin "2") (pinfunction "2_2") (pintype "passive"))
      (node (ref "C9") (pin "2") (pinfunction "2_2") (pintype "passive"))
      (node (ref "LED1") (pin "1") (pinfunction "K_1") (pintype "passive"))
      (node (ref "LED2") (pin "1") (pinfunction "K_1") (pintype "passive"))
      (node (ref "LED3") (pin "1") (pinfunction "K_1") (pintype "passive"))
      (node (ref "LED4") (pin "1") (pinfunction "K_1") (pintype "passive"))
      (node (ref "P1") (pin "1") (pinfunction "1_1") (pintype "passive"))
      (node (ref "P2") (pin "12") (pinfunction "12_12") (pintype "passive"))
      (node (ref "P2") (pin "14") (pinfunction "14_14") (pintype "passive"))
      (node (ref "P2") (pin "15") (pinfunction "15_15") (pintype "passive"))
      (node (ref "P2") (pin "17") (pinfunction "17_17") (pintype "passive"))
      (node (ref "P2") (pin "2") (pinfunction "2_2") (pintype "passive"))
      (node (ref "P2") (pin "23") (pinfunction "23_23") (pintype "passive"))
      (node (ref "P2") (pin "25") (pinfunction "25_25") (pintype "passive"))
      (node (ref "P2") (pin "27") (pinfunction "27_27") (pintype "passive"))
      (node (ref "P2") (pin "32") (pinfunction "32_32") (pintype "passive"))
      (node (ref "P2") (pin "5") (pinfunction "5_5") (pintype "passive"))
      (node (ref "P2") (pin "7") (pinfunction "7_7") (pintype "passive"))
      (node (ref "P2") (pin "9") (pinfunction "9_9") (pintype "passive"))
      (node (ref "P4") (pin "6") (pinfunction "6_6") (pintype "passive"))
      (node (ref "P4") (pin "7") (pinfunction "7_7") (pintype "passive"))
      (node (ref "P6") (pin "1") (pinfunction "1_1") (pintype "passive"))
      (node (ref "P6") (pin "2") (pinfunction "2_2") (pintype "passive"))
      (node (ref "P6") (pin "7") (pinfunction "7_7") (pintype "passive"))
      (node (ref "PS1") (pin "7") (pinfunction "-VOUT_7") (pintype "passive"))
      (node (ref "R10") (pin "1") (pinfunction "1_1") (pintype "passive"))
      (node (ref "R14") (pin "1") (pinfunction "1_1") (pintype "passive"))
      (node (ref "R16") (pin "2") (pinfunction "2_2") (pintype "passive"))
      (node (ref "R17") (pin "1") (pinfunction "1_1") (pintype "passive"))
      (node (ref "R5") (pin "2") (pinfunction "2_2") (pintype "passive"))
      (node (ref "SW1") (pin "3") (pinfunction "3_3") (pintype "passive"))
      (node (ref "SW1") (pin "4") (pinfunction "4_4") (pintype "passive"))
      (node (ref "U1") (pin "107") (pinfunction "VSS_107") (pintype "power_in"))
      (node (ref "U1") (pin "120") (pinfunction "VSS_120") (pintype "power_in"))
      (node (ref "U1") (pin "130") (pinfunction "VSS_130") (pintype "power_in"))
      (node (ref "U1") (pin "143") (pinfunction "PDR_ON_143") (pintype "input"))
      (node (ref "U1") (pin "16") (pinfunction "VSS_16") (pintype "power_in"))
      (node (ref "U1") (pin "38") (pinfunction "VSS_38") (pintype "power_in"))
      (node (ref "U1") (pin "51") (pinfunction "VSS_51") (pintype "power_in"))
      (node (ref "U1") (pin "61") (pinfunction "VSS_61") (pintype "power_in"))
      (node (ref "U1") (pin "83") (pinfunction "VSS_83") (pintype "power_in"))
      (node (ref "U1") (pin "94") (pinfunction "VSS_94") (pintype "power_in"))
      (node (ref "U10") (pin "C1") (pinfunction "GND_C1") (pintype "power_in"))
      (node (ref "U10") (pin "C3") (pinfunction "A1_C3") (pintype "input"))
      (node (ref "U2") (pin "2") (pinfunction "GND_2") (pintype "power_in"))
      (node (ref "U3") (pin "2") (pinfunction "GND_2") (pintype "power_in"))
      (node (ref "U7") (pin "2") (pinfunction "GND_2") (pintype "power_in"))
      (node (ref "U7") (pin "4") (pinfunction "GND_4") (pintype "power_in"))
      (node (ref "U8") (pin "B3") (pinfunction "A0_B3") (pintype "input"))
      (node (ref "U8") (pin "C1") (pinfunction "GND_C1") (pintype "power_in"))
      (node (ref "U8") (pin "C3") (pinfunction "A1_C3") (pintype "input"))
      (node (ref "U9") (pin "C1") (pinfunction "GND_C1") (pintype "power_in"))
      (node (ref "U9") (pin "C3") (pinfunction "A1_C3") (pintype "input"))
      (node (ref "Y1") (pin "2") (pinfunction "GND_2") (pintype "power_in"))
      (node (ref "Y2") (pin "2") (pinfunction "GND_2") (pintype "power_in"))
    )
    (net (code "66") (name "Motor_VCC") (class "Default")
      (node (ref "J3") (pin "3") (pinfunction "3_3") (pintype "passive"))
      (node (ref "R31") (pin "2") (pinfunction "2_2") (pintype "passive"))
      (node (ref "U10") (pin "D1") (pinfunction "BUS_D1") (pintype "passive"))
      (node (ref "U10") (pin "D2") (pinfunction "IN-_D2") (pintype "input"))
    )
    (net (code "67") (name "Net-(LED1-A)") (class "Default")
      (node (ref "LED1") (pin "2") (pinfunction "A_2") (pintype "passive"))
      (node (ref "R2") (pin "2") (pinfunction "2_2") (pintype "passive"))
    )
    (net (code "68") (name "Net-(LED2-A)") (class "Default")
      (node (ref "LED2") (pin "2") (pinfunction "A_2") (pintype "passive"))
      (node (ref "R4") (pin "2") (pinfunction "2_2") (pintype "passive"))
    )
    (net (code "69") (name "Net-(LED3-A)") (class "Default")
      (node (ref "LED3") (pin "2") (pinfunction "A_2") (pintype "passive"))
      (node (ref "R3") (pin "2") (pinfunction "2_2") (pintype "passive"))
    )
    (net (code "70") (name "Net-(LED4-A)") (class "Default")
      (node (ref "LED4") (pin "2") (pinfunction "A_2") (pintype "passive"))
      (node (ref "R6") (pin "2") (pinfunction "2_2") (pintype "passive"))
    )
    (net (code "71") (name "Net-(U1A-PC14-OSC32_IN(PC14))") (class "Default")
      (node (ref "U1") (pin "8") (pinfunction "PC14-OSC32_IN(PC14)_8") (pintype "bidirectional"))
      (node (ref "Y2") (pin "3") (pinfunction "CLK_Out_3") (pintype "output"))
    )
    (net (code "72") (name "Net-(U1B-PH0-OSC_IN(PH0))") (class "Default")
      (node (ref "U1") (pin "23") (pinfunction "PH0-OSC_IN(PH0)_23") (pintype "bidirectional"))
      (node (ref "Y1") (pin "3") (pinfunction "OUT_3") (pintype "passive"))
    )
    (net (code "73") (name "Net-(U1B-VCAP_1)") (class "Default")
      (node (ref "C3") (pin "1") (pinfunction "1_1") (pintype "passive"))
      (node (ref "U1") (pin "71") (pinfunction "VCAP_1_71") (pintype "passive"))
    )
    (net (code "74") (name "Net-(U1B-VCAP_2)") (class "Default")
      (node (ref "C4") (pin "1") (pinfunction "1_1") (pintype "passive"))
      (node (ref "U1") (pin "106") (pinfunction "VCAP_2_106") (pintype "passive"))
    )
    (net (code "75") (name "Net-(U2-S)") (class "Default")
      (node (ref "R10") (pin "2") (pinfunction "2_2") (pintype "passive"))
      (node (ref "U2") (pin "8") (pinfunction "S_8") (pintype "input"))
    )
    (net (code "76") (name "Net-(U3-S)") (class "Default")
      (node (ref "R14") (pin "2") (pinfunction "2_2") (pintype "passive"))
      (node (ref "U3") (pin "8") (pinfunction "S_8") (pintype "input"))
    )
    (net (code "77") (name "Net-(Y1-~{ST})") (class "Default")
      (node (ref "R1") (pin "1") (pinfunction "1_1") (pintype "passive"))
      (node (ref "Y1") (pin "1") (pinfunction "~{ST}_1") (pintype "input"))
    )
    (net (code "78") (name "PA_VCC") (class "Default")
      (node (ref "J2") (pin "3") (pinfunction "3_3") (pintype "passive"))
      (node (ref "R27") (pin "2") (pinfunction "2_2") (pintype "passive"))
      (node (ref "U9") (pin "D1") (pinfunction "BUS_D1") (pintype "passive"))
      (node (ref "U9") (pin "D2") (pinfunction "IN-_D2") (pintype "input"))
    )
    (net (code "79") (name "VDD_ANA") (class "Default")
      (node (ref "R18") (pin "2") (pinfunction "2_2") (pintype "passive"))
      (node (ref "R19") (pin "2") (pinfunction "2_2") (pintype "passive"))
    )
    (net (code "80") (name "unconnected-(P3-Pad1)") (class "Default")
      (node (ref "P3") (pin "1") (pinfunction "1_1") (pintype "passive+no_connect"))
    )
    (net (code "81") (name "unconnected-(P3-Pad2)") (class "Default")
      (node (ref "P3") (pin "2") (pinfunction "2_2") (pintype "passive+no_connect"))
    )
    (net (code "82") (name "unconnected-(P3-Pad3)") (class "Default")
      (node (ref "P3") (pin "3") (pinfunction "3_3") (pintype "passive+no_connect"))
    )
    (net (code "83") (name "unconnected-(P3-Pad4)") (class "Default")
      (node (ref "P3") (pin "4") (pinfunction "4_4") (pintype "passive+no_connect"))
    )
    (net (code "84") (name "unconnected-(P3-Pad5)") (class "Default")
      (node (ref "P3") (pin "5") (pinfunction "5_5") (pintype "passive+no_connect"))
    )
    (net (code "85") (name "unconnected-(P3-Pad6)") (class "Default")
      (node (ref "P3") (pin "6") (pinfunction "6_6") (pintype "passive+no_connect"))
    )
    (net (code "86") (name "unconnected-(P4-Pad1)") (class "Default")
      (node (ref "P4") (pin "1") (pinfunction "1_1") (pintype "passive+no_connect"))
    )
    (net (code "87") (name "unconnected-(P4-Pad2)") (class "Default")
      (node (ref "P4") (pin "2") (pinfunction "2_2") (pintype "passive+no_connect"))
    )
    (net (code "88") (name "unconnected-(P4-Pad3)") (class "Default")
      (node (ref "P4") (pin "3") (pinfunction "3_3") (pintype "passive+no_connect"))
    )
    (net (code "89") (name "unconnected-(P4-Pad8)") (class "Default")
      (node (ref "P4") (pin "8") (pinfunction "8_8") (pintype "passive+no_connect"))
    )
    (net (code "90") (name "unconnected-(P5-Pad5)") (class "Default")
      (node (ref "P5") (pin "5") (pinfunction "5_5") (pintype "passive+no_connect"))
    )
    (net (code "91") (name "unconnected-(P5-Pad6)") (class "Default")
      (node (ref "P5") (pin "6") (pinfunction "6_6") (pintype "passive+no_connect"))
    )
    (net (code "92") (name "unconnected-(P5-Pad7)") (class "Default")
      (node (ref "P5") (pin "7") (pinfunction "7_7") (pintype "passive+no_connect"))
    )
    (net (code "93") (name "unconnected-(P5-Pad8)") (class "Default")
      (node (ref "P5") (pin "8") (pinfunction "8_8") (pintype "passive+no_connect"))
    )
    (net (code "94") (name "unconnected-(P6-Pad3)") (class "Default")
      (node (ref "P6") (pin "3") (pinfunction "3_3") (pintype "passive+no_connect"))
    )
    (net (code "95") (name "unconnected-(P6-Pad4)") (class "Default")
      (node (ref "P6") (pin "4") (pinfunction "4_4") (pintype "passive+no_connect"))
    )
    (net (code "96") (name "unconnected-(P6-Pad5)") (class "Default")
      (node (ref "P6") (pin "5") (pinfunction "5_5") (pintype "passive+no_connect"))
    )
    (net (code "97") (name "unconnected-(P6-Pad6)") (class "Default")
      (node (ref "P6") (pin "6") (pinfunction "6_6") (pintype "passive+no_connect"))
    )
    (net (code "98") (name "unconnected-(P6-Pad8)") (class "Default")
      (node (ref "P6") (pin "8") (pinfunction "8_8") (pintype "passive+no_connect"))
    )
    (net (code "99") (name "unconnected-(P6-Pad9)") (class "Default")
      (node (ref "P6") (pin "9") (pinfunction "9_9") (pintype "passive+no_connect"))
    )
    (net (code "100") (name "unconnected-(P6-Pad10)") (class "Default")
      (node (ref "P6") (pin "10") (pinfunction "10_10") (pintype "passive+no_connect"))
    )
    (net (code "101") (name "unconnected-(PS1-CTRL-Pad3)") (class "Default")
      (node (ref "PS1") (pin "3") (pinfunction "CTRL_3") (pintype "passive+no_connect"))
    )
    (net (code "102") (name "unconnected-(PS1-NC-Pad8)") (class "Default")
      (node (ref "PS1") (pin "8") (pinfunction "NC_8") (pintype "passive+no_connect"))
    )
    (net (code "103") (name "unconnected-(PS1-TRIM-Pad5)") (class "Default")
      (node (ref "PS1") (pin "5") (pinfunction "TRIM_5") (pintype "passive+no_connect"))
    )
    (net (code "104") (name "unconnected-(U1A-PA8-Pad100)") (class "Default")
      (node (ref "U1") (pin "100") (pinfunction "PA8_100") (pintype "bidirectional+no_connect"))
    )
    (net (code "105") (name "unconnected-(U1A-PB1-Pad47)") (class "Default")
      (node (ref "U1") (pin "47") (pinfunction "PB1_47") (pintype "bidirectional+no_connect"))
    )
    (net (code "106") (name "unconnected-(U1A-PB2-BOOT1(PB2)-Pad48)") (class "Default")
      (node (ref "U1") (pin "48") (pinfunction "PB2-BOOT1(PB2)_48") (pintype "bidirectional+no_connect"))
    )
    (net (code "107") (name "unconnected-(U1A-PB4(NJTRST)-Pad134)") (class "Default")
      (node (ref "U1") (pin "134") (pinfunction "PB4(NJTRST)_134") (pintype "bidirectional+no_connect"))
    )
    (net (code "108") (name "unconnected-(U1A-PB5-Pad135)") (class "Default")
      (node (ref "U1") (pin "135") (pinfunction "PB5_135") (pintype "bidirectional+no_connect"))
    )
    (net (code "109") (name "unconnected-(U1A-PB6-Pad136)") (class "Default")
      (node (ref "U1") (pin "136") (pinfunction "PB6_136") (pintype "bidirectional+no_connect"))
    )
    (net (code "110") (name "unconnected-(U1A-PB7-Pad137)") (class "Default")
      (node (ref "U1") (pin "137") (pinfunction "PB7_137") (pintype "bidirectional+no_connect"))
    )
    (net (code "111") (name "unconnected-(U1A-PB8-Pad139)") (class "Default")
      (node (ref "U1") (pin "139") (pinfunction "PB8_139") (pintype "bidirectional+no_connect"))
    )
    (net (code "112") (name "unconnected-(U1A-PB14-Pad75)") (class "Default")
      (node (ref "U1") (pin "75") (pinfunction "PB14_75") (pintype "bidirectional+no_connect"))
    )
    (net (code "113") (name "unconnected-(U1A-PB15-Pad76)") (class "Default")
      (node (ref "U1") (pin "76") (pinfunction "PB15_76") (pintype "bidirectional+no_connect"))
    )
    (net (code "114") (name "unconnected-(U1A-PC0-Pad26)") (class "Default")
      (node (ref "U1") (pin "26") (pinfunction "PC0_26") (pintype "bidirectional+no_connect"))
    )
    (net (code "115") (name "unconnected-(U1A-PC1-Pad27)") (class "Default")
      (node (ref "U1") (pin "27") (pinfunction "PC1_27") (pintype "bidirectional+no_connect"))
    )
    (net (code "116") (name "unconnected-(U1A-PC2-Pad28)") (class "Default")
      (node (ref "U1") (pin "28") (pinfunction "PC2_28") (pintype "bidirectional+no_connect"))
    )
    (net (code "117") (name "unconnected-(U1A-PC3-Pad29)") (class "Default")
      (node (ref "U1") (pin "29") (pinfunction "PC3_29") (pintype "bidirectional+no_connect"))
    )
    (net (code "118") (name "unconnected-(U1A-PC8-Pad98)") (class "Default")
      (node (ref "U1") (pin "98") (pinfunction "PC8_98") (pintype "bidirectional+no_connect"))
    )
    (net (code "119") (name "unconnected-(U1A-PC9-Pad99)") (class "Default")
      (node (ref "U1") (pin "99") (pinfunction "PC9_99") (pintype "bidirectional+no_connect"))
    )
    (net (code "120") (name "unconnected-(U1A-PC13-Pad7)") (class "Default")
      (node (ref "U1") (pin "7") (pinfunction "PC13_7") (pintype "bidirectional+no_connect"))
    )
    (net (code "121") (name "unconnected-(U1A-PC15-OSC32_OUT(PC15)-Pad9)") (class "Default")
      (node (ref "U1") (pin "9") (pinfunction "PC15-OSC32_OUT(PC15)_9") (pintype "bidirectional+no_connect"))
    )
    (net (code "122") (name "unconnected-(U1A-PD0-Pad114)") (class "Default")
      (node (ref "U1") (pin "114") (pinfunction "PD0_114") (pintype "bidirectional+no_connect"))
    )
    (net (code "123") (name "unconnected-(U1A-PD1-Pad115)") (class "Default")
      (node (ref "U1") (pin "115") (pinfunction "PD1_115") (pintype "bidirectional+no_connect"))
    )
    (net (code "124") (name "unconnected-(U1A-PD2-Pad116)") (class "Default")
      (node (ref "U1") (pin "116") (pinfunction "PD2_116") (pintype "bidirectional+no_connect"))
    )
    (net (code "125") (name "unconnected-(U1A-PD3-Pad117)") (class "Default")
      (node (ref "U1") (pin "117") (pinfunction "PD3_117") (pintype "bidirectional+no_connect"))
    )
    (net (code "126") (name "unconnected-(U1A-PD4-Pad118)") (class "Default")
      (node (ref "U1") (pin "118") (pinfunction "PD4_118") (pintype "bidirectional+no_connect"))
    )
    (net (code "127") (name "unconnected-(U1A-PD5-Pad119)") (class "Default")
      (node (ref "U1") (pin "119") (pinfunction "PD5_119") (pintype "bidirectional+no_connect"))
    )
    (net (code "128") (name "unconnected-(U1A-PD6-Pad122)") (class "Default")
      (node (ref "U1") (pin "122") (pinfunction "PD6_122") (pintype "bidirectional+no_connect"))
    )
    (net (code "129") (name "unconnected-(U1A-PD7-Pad123)") (class "Default")
      (node (ref "U1") (pin "123") (pinfunction "PD7_123") (pintype "bidirectional+no_connect"))
    )
    (net (code "130") (name "unconnected-(U1A-PD8-Pad77)") (class "Default")
      (node (ref "U1") (pin "77") (pinfunction "PD8_77") (pintype "bidirectional+no_connect"))
    )
    (net (code "131") (name "unconnected-(U1A-PD9-Pad78)") (class "Default")
      (node (ref "U1") (pin "78") (pinfunction "PD9_78") (pintype "bidirectional+no_connect"))
    )
    (net (code "132") (name "unconnected-(U1A-PD10-Pad79)") (class "Default")
      (node (ref "U1") (pin "79") (pinfunction "PD10_79") (pintype "bidirectional+no_connect"))
    )
    (net (code "133") (name "unconnected-(U1A-PD11-Pad80)") (class "Default")
      (node (ref "U1") (pin "80") (pinfunction "PD11_80") (pintype "bidirectional+no_connect"))
    )
    (net (code "134") (name "unconnected-(U1A-PD12-Pad81)") (class "Default")
      (node (ref "U1") (pin "81") (pinfunction "PD12_81") (pintype "bidirectional+no_connect"))
    )
    (net (code "135") (name "unconnected-(U1A-PD13-Pad82)") (class "Default")
      (node (ref "U1") (pin "82") (pinfunction "PD13_82") (pintype "bidirectional+no_connect"))
    )
    (net (code "136") (name "unconnected-(U1A-PD14-Pad85)") (class "Default")
      (node (ref "U1") (pin "85") (pinfunction "PD14_85") (pintype "bidirectional+no_connect"))
    )
    (net (code "137") (name "unconnected-(U1A-PD15-Pad86)") (class "Default")
      (node (ref "U1") (pin "86") (pinfunction "PD15_86") (pintype "bidirectional+no_connect"))
    )
    (net (code "138") (name "unconnected-(U1A-PE3-Pad2)") (class "Default")
      (node (ref "U1") (pin "2") (pinfunction "PE3_2") (pintype "bidirectional+no_connect"))
    )
    (net (code "139") (name "unconnected-(U1A-PE7-Pad58)") (class "Default")
      (node (ref "U1") (pin "58") (pinfunction "PE7_58") (pintype "bidirectional+no_connect"))
    )
    (net (code "140") (name "unconnected-(U1A-PE8-Pad59)") (class "Default")
      (node (ref "U1") (pin "59") (pinfunction "PE8_59") (pintype "bidirectional+no_connect"))
    )
    (net (code "141") (name "unconnected-(U1A-PE9-Pad60)") (class "Default")
      (node (ref "U1") (pin "60") (pinfunction "PE9_60") (pintype "bidirectional+no_connect"))
    )
    (net (code "142") (name "unconnected-(U1A-PE10-Pad63)") (class "Default")
      (node (ref "U1") (pin "63") (pinfunction "PE10_63") (pintype "bidirectional+no_connect"))
    )
    (net (code "143") (name "unconnected-(U1A-PE11-Pad64)") (class "Default")
      (node (ref "U1") (pin "64") (pinfunction "PE11_64") (pintype "bidirectional+no_connect"))
    )
    (net (code "144") (name "unconnected-(U1A-PE12-Pad65)") (class "Default")
      (node (ref "U1") (pin "65") (pinfunction "PE12_65") (pintype "bidirectional+no_connect"))
    )
    (net (code "145") (name "unconnected-(U1A-PF0-Pad10)") (class "Default")
      (node (ref "U1") (pin "10") (pinfunction "PF0_10") (pintype "bidirectional+no_connect"))
    )
    (net (code "146") (name "unconnected-(U1A-PF1-Pad11)") (class "Default")
      (node (ref "U1") (pin "11") (pinfunction "PF1_11") (pintype "bidirectional+no_connect"))
    )
    (net (code "147") (name "unconnected-(U1A-PF2-Pad12)") (class "Default")
      (node (ref "U1") (pin "12") (pinfunction "PF2_12") (pintype "bidirectional+no_connect"))
    )
    (net (code "148") (name "unconnected-(U1A-PF3-Pad13)") (class "Default")
      (node (ref "U1") (pin "13") (pinfunction "PF3_13") (pintype "bidirectional+no_connect"))
    )
    (net (code "149") (name "unconnected-(U1A-PF4-Pad14)") (class "Default")
      (node (ref "U1") (pin "14") (pinfunction "PF4_14") (pintype "bidirectional+no_connect"))
    )
    (net (code "150") (name "unconnected-(U1A-PF5-Pad15)") (class "Default")
      (node (ref "U1") (pin "15") (pinfunction "PF5_15") (pintype "bidirectional+no_connect"))
    )
    (net (code "151") (name "unconnected-(U1A-PF6-Pad18)") (class "Default")
      (node (ref "U1") (pin "18") (pinfunction "PF6_18") (pintype "bidirectional+no_connect"))
    )
    (net (code "152") (name "unconnected-(U1A-PF7-Pad19)") (class "Default")
      (node (ref "U1") (pin "19") (pinfunction "PF7_19") (pintype "bidirectional+no_connect"))
    )
    (net (code "153") (name "unconnected-(U1A-PF8-Pad20)") (class "Default")
      (node (ref "U1") (pin "20") (pinfunction "PF8_20") (pintype "bidirectional+no_connect"))
    )
    (net (code "154") (name "unconnected-(U1A-PF9-Pad21)") (class "Default")
      (node (ref "U1") (pin "21") (pinfunction "PF9_21") (pintype "bidirectional+no_connect"))
    )
    (net (code "155") (name "unconnected-(U1A-PF10-Pad22)") (class "Default")
      (node (ref "U1") (pin "22") (pinfunction "PF10_22") (pintype "bidirectional+no_connect"))
    )
    (net (code "156") (name "unconnected-(U1A-PF11-Pad49)") (class "Default")
      (node (ref "U1") (pin "49") (pinfunction "PF11_49") (pintype "bidirectional+no_connect"))
    )
    (net (code "157") (name "unconnected-(U1A-PF12-Pad50)") (class "Default")
      (node (ref "U1") (pin "50") (pinfunction "PF12_50") (pintype "bidirectional+no_connect"))
    )
    (net (code "158") (name "unconnected-(U1A-PF13-Pad53)") (class "Default")
      (node (ref "U1") (pin "53") (pinfunction "PF13_53") (pintype "bidirectional+no_connect"))
    )
    (net (code "159") (name "unconnected-(U1A-PF14-Pad54)") (class "Default")
      (node (ref "U1") (pin "54") (pinfunction "PF14_54") (pintype "bidirectional+no_connect"))
    )
    (net (code "160") (name "unconnected-(U1A-PF15-Pad55)") (class "Default")
      (node (ref "U1") (pin "55") (pinfunction "PF15_55") (pintype "bidirectional+no_connect"))
    )
    (net (code "161") (name "unconnected-(U1B-PG0-Pad56)") (class "Default")
      (node (ref "U1") (pin "56") (pinfunction "PG0_56") (pintype "bidirectional+no_connect"))
    )
    (net (code "162") (name "unconnected-(U1B-PG1-Pad57)") (class "Default")
      (node (ref "U1") (pin "57") (pinfunction "PG1_57") (pintype "bidirectional+no_connect"))
    )
    (net (code "163") (name "unconnected-(U1B-PG6-Pad91)") (class "Default")
      (node (ref "U1") (pin "91") (pinfunction "PG6_91") (pintype "bidirectional+no_connect"))
    )
    (net (code "164") (name "unconnected-(U1B-PG7-Pad92)") (class "Default")
      (node (ref "U1") (pin "92") (pinfunction "PG7_92") (pintype "bidirectional+no_connect"))
    )
    (net (code "165") (name "unconnected-(U1B-PG8-Pad93)") (class "Default")
      (node (ref "U1") (pin "93") (pinfunction "PG8_93") (pintype "bidirectional+no_connect"))
    )
    (net (code "166") (name "unconnected-(U1B-PG12-Pad127)") (class "Default")
      (node (ref "U1") (pin "127") (pinfunction "PG12_127") (pintype "bidirectional+no_connect"))
    )
    (net (code "167") (name "unconnected-(U1B-PG13-Pad128)") (class "Default")
      (node (ref "U1") (pin "128") (pinfunction "PG13_128") (pintype "bidirectional+no_connect"))
    )
    (net (code "168") (name "unconnected-(U1B-PG14-Pad129)") (class "Default")
      (node (ref "U1") (pin "129") (pinfunction "PG14_129") (pintype "bidirectional+no_connect"))
    )
    (net (code "169") (name "unconnected-(U1B-PG15-Pad132)") (class "Default")
      (node (ref "U1") (pin "132") (pinfunction "PG15_132") (pintype "bidirectional+no_connect"))
    )
    (net (code "170") (name "unconnected-(U1B-PH1-OSC_OUT(PH1)-Pad24)") (class "Default")
      (node (ref "U1") (pin "24") (pinfunction "PH1-OSC_OUT(PH1)_24") (pintype "bidirectional+no_connect"))
    )
    (net (code "171") (name "unconnected-(U2-VREF-Pad5)") (class "Default")
      (node (ref "U2") (pin "5") (pinfunction "VREF_5") (pintype "output+no_connect"))
    )
    (net (code "172") (name "unconnected-(U3-VREF-Pad5)") (class "Default")
      (node (ref "U3") (pin "5") (pinfunction "VREF_5") (pintype "output+no_connect"))
    )
    (net (code "173") (name "unconnected-(U8-NC-PadB2)") (class "Default")
      (node (ref "U8") (pin "B2") (pinfunction "NC_B2") (pintype "passive+no_connect"))
    )
    (net (code "174") (name "unconnected-(U8-NC-PadC2)") (class "Default")
      (node (ref "U8") (pin "C2") (pinfunction "NC_C2") (pintype "passive+no_connect"))
    )
    (net (code "175") (name "unconnected-(U9-NC-PadB2)") (class "Default")
      (node (ref "U9") (pin "B2") (pinfunction "NC_B2") (pintype "passive+no_connect"))
    )
    (net (code "176") (name "unconnected-(U9-NC-PadC2)") (class "Default")
      (node (ref "U9") (pin "C2") (pinfunction "NC_C2") (pintype "passive+no_connect"))
    )
    (net (code "177") (name "unconnected-(U10-NC-PadB2)") (class "Default")
      (node (ref "U10") (pin "B2") (pinfunction "NC_B2") (pintype "passive+no_connect"))
    )
    (net (code "178") (name "unconnected-(U10-NC-PadC2)") (class "Default")
      (node (ref "U10") (pin "C2") (pinfunction "NC_C2") (pintype "passive+no_connect"))
    )
    (net (code "179") (name "unconnected-(Y2-NC-Pad1)") (class "Default")
      (node (ref "Y2") (pin "1") (pinfunction "NC_1") (pintype "passive+no_connect"))
    )
  )
)
